# Current_Sensing.net
KiCad netlist of a schematic drawn in Altium Designer
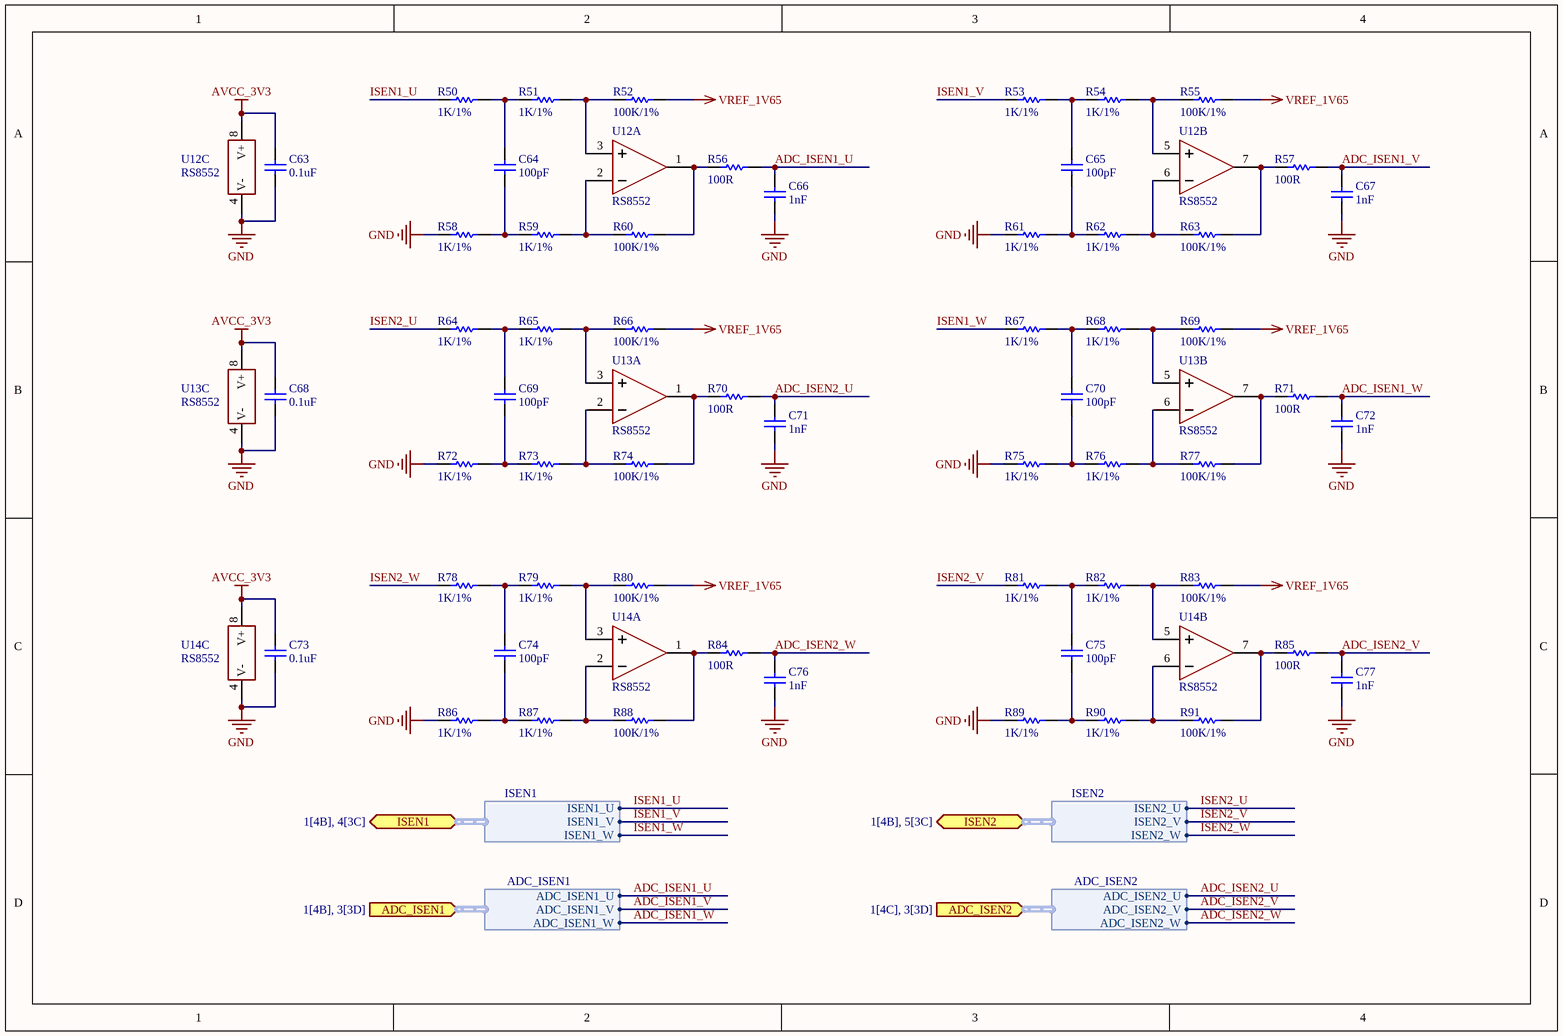
[diagram p0: Current_Sensing.SchDoc]

(export (version "E")
  (design (tool "Eeschema 10.0.6"))
  (components
    (comp (ref "C63")
      (value "0.1uF")
      (footprint "C0603_NS")
      (description "Capacitor")
      (libsource (lib "Miscellaneous Devices") (part "Cap"))
    )
    (comp (ref "C64")
      (value "100pF")
      (footprint "C0603_NS")
      (description "Capacitor")
      (libsource (lib "Miscellaneous Devices") (part "Cap"))
    )
    (comp (ref "C65")
      (value "100pF")
      (footprint "C0603_NS")
      (description "Capacitor")
      (libsource (lib "Miscellaneous Devices") (part "Cap"))
    )
    (comp (ref "C66")
      (value "1nF")
      (footprint "C0603_NS")
      (description "Capacitor")
      (libsource (lib "Miscellaneous Devices") (part "Cap"))
    )
    (comp (ref "C67")
      (value "1nF")
      (footprint "C0603_NS")
      (description "Capacitor")
      (libsource (lib "Miscellaneous Devices") (part "Cap"))
    )
    (comp (ref "C68")
      (value "0.1uF")
      (footprint "C0603_NS")
      (description "Capacitor")
      (libsource (lib "Miscellaneous Devices") (part "Cap"))
    )
    (comp (ref "C69")
      (value "100pF")
      (footprint "C0603_NS")
      (description "Capacitor")
      (libsource (lib "Miscellaneous Devices") (part "Cap"))
    )
    (comp (ref "C70")
      (value "100pF")
      (footprint "C0603_NS")
      (description "Capacitor")
      (libsource (lib "Miscellaneous Devices") (part "Cap"))
    )
    (comp (ref "C71")
      (value "1nF")
      (footprint "C0603_NS")
      (description "Capacitor")
      (libsource (lib "Miscellaneous Devices") (part "Cap"))
    )
    (comp (ref "C72")
      (value "1nF")
      (footprint "C0603_NS")
      (description "Capacitor")
      (libsource (lib "Miscellaneous Devices") (part "Cap"))
    )
    (comp (ref "C73")
      (value "0.1uF")
      (footprint "C0603_NS")
      (description "Capacitor")
      (libsource (lib "Miscellaneous Devices") (part "Cap"))
    )
    (comp (ref "C74")
      (value "100pF")
      (footprint "C0603_NS")
      (description "Capacitor")
      (libsource (lib "Miscellaneous Devices") (part "Cap"))
    )
    (comp (ref "C75")
      (value "100pF")
      (footprint "C0603_NS")
      (description "Capacitor")
      (libsource (lib "Miscellaneous Devices") (part "Cap"))
    )
    (comp (ref "C76")
      (value "1nF")
      (footprint "C0603_NS")
      (description "Capacitor")
      (libsource (lib "Miscellaneous Devices") (part "Cap"))
    )
    (comp (ref "C77")
      (value "1nF")
      (footprint "C0603_NS")
      (description "Capacitor")
      (libsource (lib "Miscellaneous Devices") (part "Cap"))
    )
    (comp (ref "R50")
      (value "1K/1%")
      (footprint "R0603_NS")
      (description "Resistor")
      (libsource (lib "Miscellaneous Devices") (part "Res1"))
    )
    (comp (ref "R51")
      (value "1K/1%")
      (footprint "R0603_NS")
      (description "Resistor")
      (libsource (lib "Miscellaneous Devices") (part "Res1"))
    )
    (comp (ref "R52")
      (value "100K/1%")
      (footprint "R0603_NS")
      (description "Resistor")
      (libsource (lib "Miscellaneous Devices") (part "Res1"))
    )
    (comp (ref "R53")
      (value "1K/1%")
      (footprint "R0603_NS")
      (description "Resistor")
      (libsource (lib "Miscellaneous Devices") (part "Res1"))
    )
    (comp (ref "R54")
      (value "1K/1%")
      (footprint "R0603_NS")
      (description "Resistor")
      (libsource (lib "Miscellaneous Devices") (part "Res1"))
    )
    (comp (ref "R55")
      (value "100K/1%")
      (footprint "R0603_NS")
      (description "Resistor")
      (libsource (lib "Miscellaneous Devices") (part "Res1"))
    )
    (comp (ref "R56")
      (value "100R")
      (footprint "R0603_NS")
      (description "Resistor")
      (libsource (lib "Miscellaneous Devices") (part "Res1"))
    )
    (comp (ref "R57")
      (value "100R")
      (footprint "R0603_NS")
      (description "Resistor")
      (libsource (lib "Miscellaneous Devices") (part "Res1"))
    )
    (comp (ref "R58")
      (value "1K/1%")
      (footprint "R0603_NS")
      (description "Resistor")
      (libsource (lib "Miscellaneous Devices") (part "Res1"))
    )
    (comp (ref "R59")
      (value "1K/1%")
      (footprint "R0603_NS")
      (description "Resistor")
      (libsource (lib "Miscellaneous Devices") (part "Res1"))
    )
    (comp (ref "R60")
      (value "100K/1%")
      (footprint "R0603_NS")
      (description "Resistor")
      (libsource (lib "Miscellaneous Devices") (part "Res1"))
    )
    (comp (ref "R61")
      (value "1K/1%")
      (footprint "R0603_NS")
      (description "Resistor")
      (libsource (lib "Miscellaneous Devices") (part "Res1"))
    )
    (comp (ref "R62")
      (value "1K/1%")
      (footprint "R0603_NS")
      (description "Resistor")
      (libsource (lib "Miscellaneous Devices") (part "Res1"))
    )
    (comp (ref "R63")
      (value "100K/1%")
      (footprint "R0603_NS")
      (description "Resistor")
      (libsource (lib "Miscellaneous Devices") (part "Res1"))
    )
    (comp (ref "R64")
      (value "1K/1%")
      (footprint "R0603_NS")
      (description "Resistor")
      (libsource (lib "Miscellaneous Devices") (part "Res1"))
    )
    (comp (ref "R65")
      (value "1K/1%")
      (footprint "R0603_NS")
      (description "Resistor")
      (libsource (lib "Miscellaneous Devices") (part "Res1"))
    )
    (comp (ref "R66")
      (value "100K/1%")
      (footprint "R0603_NS")
      (description "Resistor")
      (libsource (lib "Miscellaneous Devices") (part "Res1"))
    )
    (comp (ref "R67")
      (value "1K/1%")
      (footprint "R0603_NS")
      (description "Resistor")
      (libsource (lib "Miscellaneous Devices") (part "Res1"))
    )
    (comp (ref "R68")
      (value "1K/1%")
      (footprint "R0603_NS")
      (description "Resistor")
      (libsource (lib "Miscellaneous Devices") (part "Res1"))
    )
    (comp (ref "R69")
      (value "100K/1%")
      (footprint "R0603_NS")
      (description "Resistor")
      (libsource (lib "Miscellaneous Devices") (part "Res1"))
    )
    (comp (ref "R70")
      (value "100R")
      (footprint "R0603_NS")
      (description "Resistor")
      (libsource (lib "Miscellaneous Devices") (part "Res1"))
    )
    (comp (ref "R71")
      (value "100R")
      (footprint "R0603_NS")
      (description "Resistor")
      (libsource (lib "Miscellaneous Devices") (part "Res1"))
    )
    (comp (ref "R72")
      (value "1K/1%")
      (footprint "R0603_NS")
      (description "Resistor")
      (libsource (lib "Miscellaneous Devices") (part "Res1"))
    )
    (comp (ref "R73")
      (value "1K/1%")
      (footprint "R0603_NS")
      (description "Resistor")
      (libsource (lib "Miscellaneous Devices") (part "Res1"))
    )
    (comp (ref "R74")
      (value "100K/1%")
      (footprint "R0603_NS")
      (description "Resistor")
      (libsource (lib "Miscellaneous Devices") (part "Res1"))
    )
    (comp (ref "R75")
      (value "1K/1%")
      (footprint "R0603_NS")
      (description "Resistor")
      (libsource (lib "Miscellaneous Devices") (part "Res1"))
    )
    (comp (ref "R76")
      (value "1K/1%")
      (footprint "R0603_NS")
      (description "Resistor")
      (libsource (lib "Miscellaneous Devices") (part "Res1"))
    )
    (comp (ref "R77")
      (value "100K/1%")
      (footprint "R0603_NS")
      (description "Resistor")
      (libsource (lib "Miscellaneous Devices") (part "Res1"))
    )
    (comp (ref "R78")
      (value "1K/1%")
      (footprint "R0603_NS")
      (description "Resistor")
      (libsource (lib "Miscellaneous Devices") (part "Res1"))
    )
    (comp (ref "R79")
      (value "1K/1%")
      (footprint "R0603_NS")
      (description "Resistor")
      (libsource (lib "Miscellaneous Devices") (part "Res1"))
    )
    (comp (ref "R80")
      (value "100K/1%")
      (footprint "R0603_NS")
      (description "Resistor")
      (libsource (lib "Miscellaneous Devices") (part "Res1"))
    )
    (comp (ref "R81")
      (value "1K/1%")
      (footprint "R0603_NS")
      (description "Resistor")
      (libsource (lib "Miscellaneous Devices") (part "Res1"))
    )
    (comp (ref "R82")
      (value "1K/1%")
      (footprint "R0603_NS")
      (description "Resistor")
      (libsource (lib "Miscellaneous Devices") (part "Res1"))
    )
    (comp (ref "R83")
      (value "100K/1%")
      (footprint "R0603_NS")
      (description "Resistor")
      (libsource (lib "Miscellaneous Devices") (part "Res1"))
    )
    (comp (ref "R84")
      (value "100R")
      (footprint "R0603_NS")
      (description "Resistor")
      (libsource (lib "Miscellaneous Devices") (part "Res1"))
    )
    (comp (ref "R85")
      (value "100R")
      (footprint "R0603_NS")
      (description "Resistor")
      (libsource (lib "Miscellaneous Devices") (part "Res1"))
    )
    (comp (ref "R86")
      (value "1K/1%")
      (footprint "R0603_NS")
      (description "Resistor")
      (libsource (lib "Miscellaneous Devices") (part "Res1"))
    )
    (comp (ref "R87")
      (value "1K/1%")
      (footprint "R0603_NS")
      (description "Resistor")
      (libsource (lib "Miscellaneous Devices") (part "Res1"))
    )
    (comp (ref "R88")
      (value "100K/1%")
      (footprint "R0603_NS")
      (description "Resistor")
      (libsource (lib "Miscellaneous Devices") (part "Res1"))
    )
    (comp (ref "R89")
      (value "1K/1%")
      (footprint "R0603_NS")
      (description "Resistor")
      (libsource (lib "Miscellaneous Devices") (part "Res1"))
    )
    (comp (ref "R90")
      (value "1K/1%")
      (footprint "R0603_NS")
      (description "Resistor")
      (libsource (lib "Miscellaneous Devices") (part "Res1"))
    )
    (comp (ref "R91")
      (value "100K/1%")
      (footprint "R0603_NS")
      (description "Resistor")
      (libsource (lib "Miscellaneous Devices") (part "Res1"))
    )
    (comp (ref "U12") (value "RS8552") (footprint "TSSOP8_N") (libsource (lib "my_library") (part "AD8606")))
    (comp (ref "U13") (value "RS8552") (footprint "TSSOP8_N") (libsource (lib "my_library") (part "AD8606")))
    (comp (ref "U14") (value "RS8552") (footprint "TSSOP8_N") (libsource (lib "my_library") (part "AD8606")))
  )
  (nets
    (net (code "5") (name "/ADC_ISEN1_U") (class "Default")
      (node (ref "C66") (pin "2") (pinfunction "2_2") (pintype "passive"))
      (node (ref "R56") (pin "2") (pinfunction "2_2") (pintype "passive"))
    )
    (net (code "6") (name "/ADC_ISEN1_V") (class "Default")
      (node (ref "C67") (pin "2") (pinfunction "2_2") (pintype "passive"))
      (node (ref "R57") (pin "2") (pinfunction "2_2") (pintype "passive"))
    )
    (net (code "7") (name "/ADC_ISEN1_W") (class "Default")
      (node (ref "C72") (pin "2") (pinfunction "2_2") (pintype "passive"))
      (node (ref "R71") (pin "2") (pinfunction "2_2") (pintype "passive"))
    )
    (net (code "8") (name "/ADC_ISEN2_U") (class "Default")
      (node (ref "C71") (pin "2") (pinfunction "2_2") (pintype "passive"))
      (node (ref "R70") (pin "2") (pinfunction "2_2") (pintype "passive"))
    )
    (net (code "9") (name "/ADC_ISEN2_V") (class "Default")
      (node (ref "C77") (pin "2") (pinfunction "2_2") (pintype "passive"))
      (node (ref "R85") (pin "2") (pinfunction "2_2") (pintype "passive"))
    )
    (net (code "10") (name "/ADC_ISEN2_W") (class "Default")
      (node (ref "C76") (pin "2") (pinfunction "2_2") (pintype "passive"))
      (node (ref "R84") (pin "2") (pinfunction "2_2") (pintype "passive"))
    )
    (net (code "11") (name "/ISEN1_U") (class "Default")
      (node (ref "R50") (pin "1") (pinfunction "1_1") (pintype "passive"))
    )
    (net (code "12") (name "/ISEN1_V") (class "Default")
      (node (ref "R53") (pin "1") (pinfunction "1_1") (pintype "passive"))
    )
    (net (code "13") (name "/ISEN1_W") (class "Default")
      (node (ref "R67") (pin "1") (pinfunction "1_1") (pintype "passive"))
    )
    (net (code "14") (name "/ISEN2_U") (class "Default")
      (node (ref "R64") (pin "1") (pinfunction "1_1") (pintype "passive"))
    )
    (net (code "15") (name "/ISEN2_V") (class "Default")
      (node (ref "R81") (pin "1") (pinfunction "1_1") (pintype "passive"))
    )
    (net (code "16") (name "/ISEN2_W") (class "Default")
      (node (ref "R78") (pin "1") (pinfunction "1_1") (pintype "passive"))
    )
    (net (code "21") (name "AVCC_3V3") (class "Default")
      (node (ref "C63") (pin "2") (pinfunction "2_2") (pintype "passive"))
      (node (ref "C68") (pin "2") (pinfunction "2_2") (pintype "passive"))
      (node (ref "C73") (pin "2") (pinfunction "2_2") (pintype "passive"))
      (node (ref "U12") (pin "8") (pinfunction "V+_8") (pintype "power_in"))
      (node (ref "U13") (pin "8") (pinfunction "V+_8") (pintype "power_in"))
      (node (ref "U14") (pin "8") (pinfunction "V+_8") (pintype "power_in"))
    )
    (net (code "22") (name "GND") (class "Default")
      (node (ref "C63") (pin "1") (pinfunction "1_1") (pintype "passive"))
      (node (ref "C66") (pin "1") (pinfunction "1_1") (pintype "passive"))
      (node (ref "C67") (pin "1") (pinfunction "1_1") (pintype "passive"))
      (node (ref "C68") (pin "1") (pinfunction "1_1") (pintype "passive"))
      (node (ref "C71") (pin "1") (pinfunction "1_1") (pintype "passive"))
      (node (ref "C72") (pin "1") (pinfunction "1_1") (pintype "passive"))
      (node (ref "C73") (pin "1") (pinfunction "1_1") (pintype "passive"))
      (node (ref "C76") (pin "1") (pinfunction "1_1") (pintype "passive"))
      (node (ref "C77") (pin "1") (pinfunction "1_1") (pintype "passive"))
      (node (ref "R58") (pin "1") (pinfunction "1_1") (pintype "passive"))
      (node (ref "R61") (pin "1") (pinfunction "1_1") (pintype "passive"))
      (node (ref "R72") (pin "1") (pinfunction "1_1") (pintype "passive"))
      (node (ref "R75") (pin "1") (pinfunction "1_1") (pintype "passive"))
      (node (ref "R86") (pin "1") (pinfunction "1_1") (pintype "passive"))
      (node (ref "R89") (pin "1") (pinfunction "1_1") (pintype "passive"))
      (node (ref "U12") (pin "4") (pinfunction "V-_4") (pintype "power_in"))
      (node (ref "U13") (pin "4") (pinfunction "V-_4") (pintype "power_in"))
      (node (ref "U14") (pin "4") (pinfunction "V-_4") (pintype "power_in"))
    )
    (net (code "23") (name "Net-(C64-Pad1)") (class "Default")
      (node (ref "C64") (pin "1") (pinfunction "1_1") (pintype "passive"))
      (node (ref "R58") (pin "2") (pinfunction "2_2") (pintype "passive"))
      (node (ref "R59") (pin "1") (pinfunction "1_1") (pintype "passive"))
    )
    (net (code "24") (name "Net-(C64-Pad2)") (class "Default")
      (node (ref "C64") (pin "2") (pinfunction "2_2") (pintype "passive"))
      (node (ref "R50") (pin "2") (pinfunction "2_2") (pintype "passive"))
      (node (ref "R51") (pin "1") (pinfunction "1_1") (pintype "passive"))
    )
    (net (code "25") (name "Net-(C65-Pad1)") (class "Default")
      (node (ref "C65") (pin "1") (pinfunction "1_1") (pintype "passive"))
      (node (ref "R61") (pin "2") (pinfunction "2_2") (pintype "passive"))
      (node (ref "R62") (pin "1") (pinfunction "1_1") (pintype "passive"))
    )
    (net (code "26") (name "Net-(C65-Pad2)") (class "Default")
      (node (ref "C65") (pin "2") (pinfunction "2_2") (pintype "passive"))
      (node (ref "R53") (pin "2") (pinfunction "2_2") (pintype "passive"))
      (node (ref "R54") (pin "1") (pinfunction "1_1") (pintype "passive"))
    )
    (net (code "27") (name "Net-(C69-Pad1)") (class "Default")
      (node (ref "C69") (pin "1") (pinfunction "1_1") (pintype "passive"))
      (node (ref "R72") (pin "2") (pinfunction "2_2") (pintype "passive"))
      (node (ref "R73") (pin "1") (pinfunction "1_1") (pintype "passive"))
    )
    (net (code "28") (name "Net-(C69-Pad2)") (class "Default")
      (node (ref "C69") (pin "2") (pinfunction "2_2") (pintype "passive"))
      (node (ref "R64") (pin "2") (pinfunction "2_2") (pintype "passive"))
      (node (ref "R65") (pin "1") (pinfunction "1_1") (pintype "passive"))
    )
    (net (code "29") (name "Net-(C70-Pad1)") (class "Default")
      (node (ref "C70") (pin "1") (pinfunction "1_1") (pintype "passive"))
      (node (ref "R75") (pin "2") (pinfunction "2_2") (pintype "passive"))
      (node (ref "R76") (pin "1") (pinfunction "1_1") (pintype "passive"))
    )
    (net (code "30") (name "Net-(C70-Pad2)") (class "Default")
      (node (ref "C70") (pin "2") (pinfunction "2_2") (pintype "passive"))
      (node (ref "R67") (pin "2") (pinfunction "2_2") (pintype "passive"))
      (node (ref "R68") (pin "1") (pinfunction "1_1") (pintype "passive"))
    )
    (net (code "31") (name "Net-(C74-Pad1)") (class "Default")
      (node (ref "C74") (pin "1") (pinfunction "1_1") (pintype "passive"))
      (node (ref "R86") (pin "2") (pinfunction "2_2") (pintype "passive"))
      (node (ref "R87") (pin "1") (pinfunction "1_1") (pintype "passive"))
    )
    (net (code "32") (name "Net-(C74-Pad2)") (class "Default")
      (node (ref "C74") (pin "2") (pinfunction "2_2") (pintype "passive"))
      (node (ref "R78") (pin "2") (pinfunction "2_2") (pintype "passive"))
      (node (ref "R79") (pin "1") (pinfunction "1_1") (pintype "passive"))
    )
    (net (code "33") (name "Net-(C75-Pad1)") (class "Default")
      (node (ref "C75") (pin "1") (pinfunction "1_1") (pintype "passive"))
      (node (ref "R89") (pin "2") (pinfunction "2_2") (pintype "passive"))
      (node (ref "R90") (pin "1") (pinfunction "1_1") (pintype "passive"))
    )
    (net (code "34") (name "Net-(C75-Pad2)") (class "Default")
      (node (ref "C75") (pin "2") (pinfunction "2_2") (pintype "passive"))
      (node (ref "R81") (pin "2") (pinfunction "2_2") (pintype "passive"))
      (node (ref "R82") (pin "1") (pinfunction "1_1") (pintype "passive"))
    )
    (net (code "35") (name "Net-(U12A-+IN_A)") (class "Default")
      (node (ref "R51") (pin "2") (pinfunction "2_2") (pintype "passive"))
      (node (ref "R52") (pin "1") (pinfunction "1_1") (pintype "passive"))
      (node (ref "U12") (pin "3") (pinfunction "+IN_A_3") (pintype "passive"))
    )
    (net (code "36") (name "Net-(U12A--IN_A)") (class "Default")
      (node (ref "R59") (pin "2") (pinfunction "2_2") (pintype "passive"))
      (node (ref "R60") (pin "1") (pinfunction "1_1") (pintype "passive"))
      (node (ref "U12") (pin "2") (pinfunction "-IN_A_2") (pintype "passive"))
    )
    (net (code "37") (name "Net-(U12A-OUT_A)") (class "Default")
      (node (ref "R56") (pin "1") (pinfunction "1_1") (pintype "passive"))
      (node (ref "R60") (pin "2") (pinfunction "2_2") (pintype "passive"))
      (node (ref "U12") (pin "1") (pinfunction "OUT_A_1") (pintype "passive"))
    )
    (net (code "38") (name "Net-(U12B-+IN_B)") (class "Default")
      (node (ref "R54") (pin "2") (pinfunction "2_2") (pintype "passive"))
      (node (ref "R55") (pin "1") (pinfunction "1_1") (pintype "passive"))
      (node (ref "U12") (pin "5") (pinfunction "+IN_B_5") (pintype "passive"))
    )
    (net (code "39") (name "Net-(U12B--IN_B)") (class "Default")
      (node (ref "R62") (pin "2") (pinfunction "2_2") (pintype "passive"))
      (node (ref "R63") (pin "1") (pinfunction "1_1") (pintype "passive"))
      (node (ref "U12") (pin "6") (pinfunction "-IN_B_6") (pintype "passive"))
    )
    (net (code "40") (name "Net-(U12B-OUT_B)") (class "Default")
      (node (ref "R57") (pin "1") (pinfunction "1_1") (pintype "passive"))
      (node (ref "R63") (pin "2") (pinfunction "2_2") (pintype "passive"))
      (node (ref "U12") (pin "7") (pinfunction "OUT_B_7") (pintype "passive"))
    )
    (net (code "41") (name "Net-(U13A-+IN_A)") (class "Default")
      (node (ref "R65") (pin "2") (pinfunction "2_2") (pintype "passive"))
      (node (ref "R66") (pin "1") (pinfunction "1_1") (pintype "passive"))
      (node (ref "U13") (pin "3") (pinfunction "+IN_A_3") (pintype "passive"))
    )
    (net (code "42") (name "Net-(U13A--IN_A)") (class "Default")
      (node (ref "R73") (pin "2") (pinfunction "2_2") (pintype "passive"))
      (node (ref "R74") (pin "1") (pinfunction "1_1") (pintype "passive"))
      (node (ref "U13") (pin "2") (pinfunction "-IN_A_2") (pintype "passive"))
    )
    (net (code "43") (name "Net-(U13A-OUT_A)") (class "Default")
      (node (ref "R70") (pin "1") (pinfunction "1_1") (pintype "passive"))
      (node (ref "R74") (pin "2") (pinfunction "2_2") (pintype "passive"))
      (node (ref "U13") (pin "1") (pinfunction "OUT_A_1") (pintype "passive"))
    )
    (net (code "44") (name "Net-(U13B-+IN_B)") (class "Default")
      (node (ref "R68") (pin "2") (pinfunction "2_2") (pintype "passive"))
      (node (ref "R69") (pin "1") (pinfunction "1_1") (pintype "passive"))
      (node (ref "U13") (pin "5") (pinfunction "+IN_B_5") (pintype "passive"))
    )
    (net (code "45") (name "Net-(U13B--IN_B)") (class "Default")
      (node (ref "R76") (pin "2") (pinfunction "2_2") (pintype "passive"))
      (node (ref "R77") (pin "1") (pinfunction "1_1") (pintype "passive"))
      (node (ref "U13") (pin "6") (pinfunction "-IN_B_6") (pintype "passive"))
    )
    (net (code "46") (name "Net-(U13B-OUT_B)") (class "Default")
      (node (ref "R71") (pin "1") (pinfunction "1_1") (pintype "passive"))
      (node (ref "R77") (pin "2") (pinfunction "2_2") (pintype "passive"))
      (node (ref "U13") (pin "7") (pinfunction "OUT_B_7") (pintype "passive"))
    )
    (net (code "47") (name "Net-(U14A-+IN_A)") (class "Default")
      (node (ref "R79") (pin "2") (pinfunction "2_2") (pintype "passive"))
      (node (ref "R80") (pin "1") (pinfunction "1_1") (pintype "passive"))
      (node (ref "U14") (pin "3") (pinfunction "+IN_A_3") (pintype "passive"))
    )
    (net (code "48") (name "Net-(U14A--IN_A)") (class "Default")
      (node (ref "R87") (pin "2") (pinfunction "2_2") (pintype "passive"))
      (node (ref "R88") (pin "1") (pinfunction "1_1") (pintype "passive"))
      (node (ref "U14") (pin "2") (pinfunction "-IN_A_2") (pintype "passive"))
    )
    (net (code "49") (name "Net-(U14A-OUT_A)") (class "Default")
      (node (ref "R84") (pin "1") (pinfunction "1_1") (pintype "passive"))
      (node (ref "R88") (pin "2") (pinfunction "2_2") (pintype "passive"))
      (node (ref "U14") (pin "1") (pinfunction "OUT_A_1") (pintype "passive"))
    )
    (net (code "50") (name "Net-(U14B-+IN_B)") (class "Default")
      (node (ref "R82") (pin "2") (pinfunction "2_2") (pintype "passive"))
      (node (ref "R83") (pin "1") (pinfunction "1_1") (pintype "passive"))
      (node (ref "U14") (pin "5") (pinfunction "+IN_B_5") (pintype "passive"))
    )
    (net (code "51") (name "Net-(U14B--IN_B)") (class "Default")
      (node (ref "R90") (pin "2") (pinfunction "2_2") (pintype "passive"))
      (node (ref "R91") (pin "1") (pinfunction "1_1") (pintype "passive"))
      (node (ref "U14") (pin "6") (pinfunction "-IN_B_6") (pintype "passive"))
    )
    (net (code "52") (name "Net-(U14B-OUT_B)") (class "Default")
      (node (ref "R85") (pin "1") (pinfunction "1_1") (pintype "passive"))
      (node (ref "R91") (pin "2") (pinfunction "2_2") (pintype "passive"))
      (node (ref "U14") (pin "7") (pinfunction "OUT_B_7") (pintype "passive"))
    )
    (net (code "53") (name "VREF_1V65") (class "Default")
      (node (ref "R52") (pin "2") (pinfunction "2_2") (pintype "passive"))
      (node (ref "R55") (pin "2") (pinfunction "2_2") (pintype "passive"))
      (node (ref "R66") (pin "2") (pinfunction "2_2") (pintype "passive"))
      (node (ref "R69") (pin "2") (pinfunction "2_2") (pintype "passive"))
      (node (ref "R80") (pin "2") (pinfunction "2_2") (pintype "passive"))
      (node (ref "R83") (pin "2") (pinfunction "2_2") (pintype "passive"))
    )
  )
)
